# transmitter.net
KiCad netlist of a schematic drawn in EAGLE
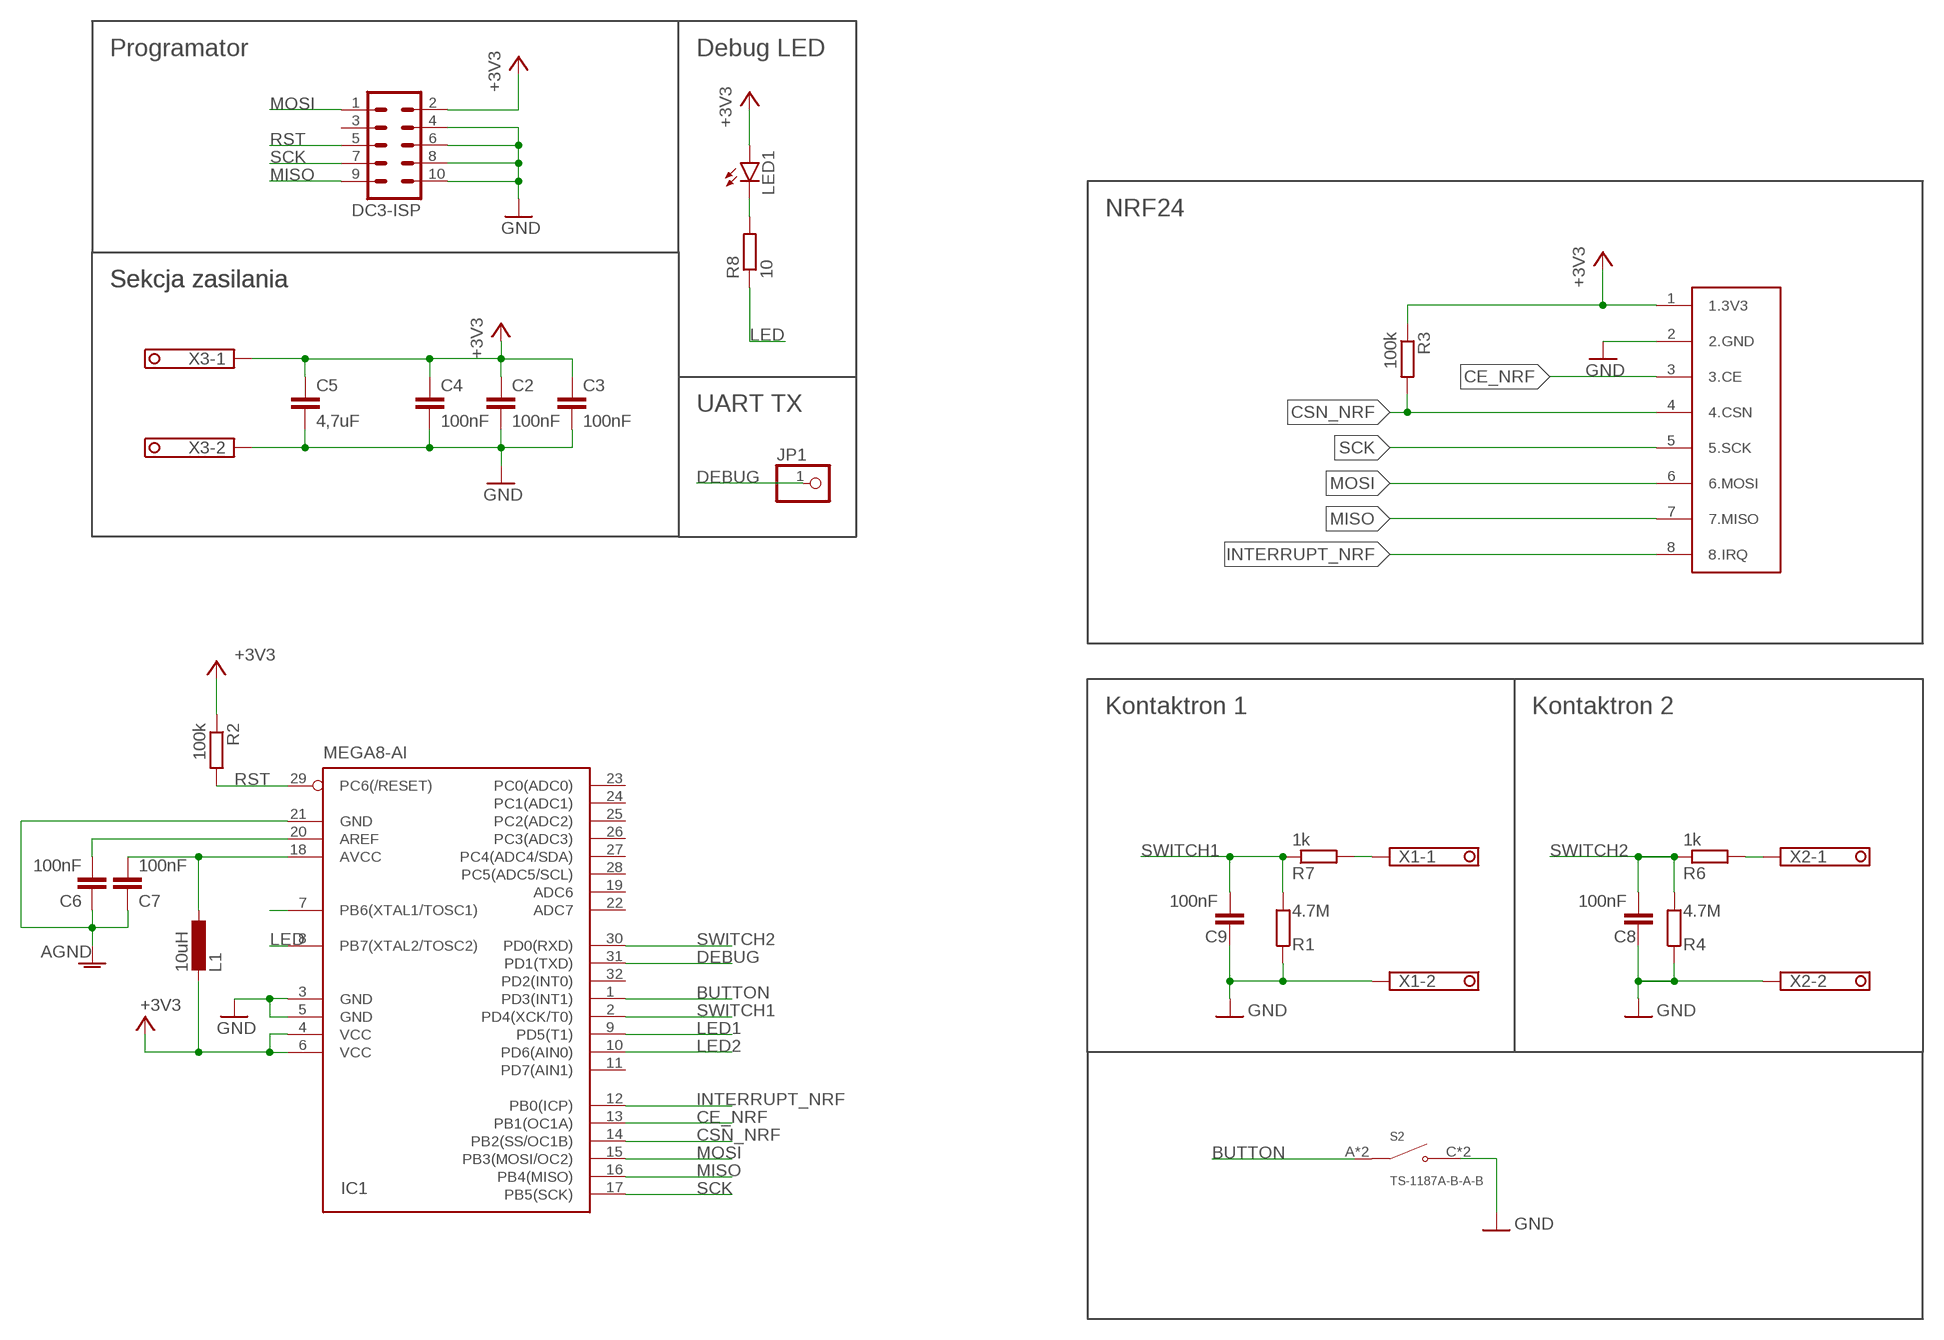
[diagram p0: schematic, sheet 1]

(export (version "E")
  (design (tool "Eeschema 10.0.6"))
  (components
    (comp (ref "C2")
      (value "100nF")
      (footprint "eagle-import:C0805")
      (libsource (lib "eagle-import") (part "C-EUC0805"))
    )
    (comp (ref "C3")
      (value "100nF")
      (footprint "eagle-import:C0805")
      (libsource (lib "eagle-import") (part "C-EUC0805"))
    )
    (comp (ref "C4")
      (value "100nF")
      (footprint "eagle-import:C0805")
      (libsource (lib "eagle-import") (part "C-EUC0805"))
    )
    (comp (ref "C5")
      (value "4,7uF")
      (footprint "eagle-import:C025-050X050")
      (libsource (lib "eagle-import") (part "C-EU025-050X050"))
    )
    (comp (ref "C6")
      (value "100nF")
      (footprint "eagle-import:C0805")
      (libsource (lib "eagle-import") (part "C-EUC0805"))
    )
    (comp (ref "C7")
      (value "100nF")
      (footprint "eagle-import:C0805")
      (libsource (lib "eagle-import") (part "C-EUC0805"))
    )
    (comp (ref "C8")
      (value "100nF")
      (footprint "eagle-import:C0805")
      (libsource (lib "eagle-import") (part "C-EUC0805"))
    )
    (comp (ref "C9")
      (value "100nF")
      (footprint "eagle-import:C0805")
      (libsource (lib "eagle-import") (part "C-EUC0805"))
    )
    (comp (ref "DC3-ISP")
      (value "ML10")
      (footprint "eagle-import:ML10")
      (libsource (lib "eagle-import") (part "ML10"))
    )
    (comp (ref "IC1")
      (value "MEGA8-AI")
      (footprint "eagle-import:TQFP32-08")
      (fields (field (name "MPN") "ATMEGA8-16AU"))
      (libsource (lib "eagle-import") (part "MEGA8-AI"))
    )
    (comp (ref "JP1")
      (value "PINHD-1X1")
      (footprint "eagle-import:1X01")
      (libsource (lib "eagle-import") (part "PINHD-1X1"))
    )
    (comp (ref "L1")
      (value "10uH")
      (footprint "eagle-import:L2012C")
      (libsource (lib "eagle-import") (part "L-EUL2012C"))
    )
    (comp (ref "LED1")
      (value "LEDCHIP-LED0805")
      (footprint "eagle-import:CHIP-LED0805")
      (libsource (lib "eagle-import") (part "LEDCHIP-LED0805"))
    )
    (comp (ref "R1")
      (value "4.7M")
      (footprint "eagle-import:M0805")
      (libsource (lib "eagle-import") (part "R-EU_M0805"))
    )
    (comp (ref "R2")
      (value "100k")
      (footprint "eagle-import:M0805")
      (libsource (lib "eagle-import") (part "R-EU_M0805"))
    )
    (comp (ref "R3")
      (value "100k")
      (footprint "eagle-import:M0805")
      (libsource (lib "eagle-import") (part "R-EU_M0805"))
    )
    (comp (ref "R4")
      (value "4.7M")
      (footprint "eagle-import:M0805")
      (libsource (lib "eagle-import") (part "R-EU_M0805"))
    )
    (comp (ref "R6")
      (value "1k")
      (footprint "eagle-import:M0805")
      (libsource (lib "eagle-import") (part "R-EU_M0805"))
    )
    (comp (ref "R7")
      (value "1k")
      (footprint "eagle-import:M0805")
      (libsource (lib "eagle-import") (part "R-EU_M0805"))
    )
    (comp (ref "R8")
      (value "10")
      (footprint "eagle-import:M0805")
      (libsource (lib "eagle-import") (part "R-EU_M0805"))
    )
    (comp (ref "S2")
      (value "TS-1187A-B-A-B")
      (footprint "eagle-import:SW_TS-1187A-B-A-B")
      (libsource (lib "eagle-import") (part "TS-1187A-B-A-B"))
    )
    (comp (ref "U$1")
      (value "NRF24L01+")
      (footprint "eagle-import:NRF24L01+")
      (libsource (lib "eagle-import") (part "NRF24L01+"))
    )
    (comp (ref "X1")
      (value "ARK-3.5MMAPC2")
      (footprint "eagle-import:1751248")
      (libsource (lib "eagle-import") (part "ARK-3.5MMAPC2"))
    )
    (comp (ref "X2")
      (value "ARK-3.5MMAPC2")
      (footprint "eagle-import:1751248")
      (libsource (lib "eagle-import") (part "ARK-3.5MMAPC2"))
    )
    (comp (ref "X3")
      (value "ARK-3.5MMAPC2")
      (footprint "eagle-import:1751248")
      (libsource (lib "eagle-import") (part "ARK-3.5MMAPC2"))
    )
  )
  (nets
    (net (code "1") (name "+3V3") (class "Default")
      (node (ref "C2") (pin "1") (pinfunction "1_1") (pintype "passive"))
      (node (ref "C3") (pin "1") (pinfunction "1_1") (pintype "passive"))
      (node (ref "C4") (pin "1") (pinfunction "1_1") (pintype "passive"))
      (node (ref "C5") (pin "1") (pinfunction "1_1") (pintype "passive"))
      (node (ref "DC3-ISP") (pin "2") (pinfunction "2_2") (pintype "passive"))
      (node (ref "IC1") (pin "4") (pinfunction "VCC_4") (pintype "power_in"))
      (node (ref "IC1") (pin "6") (pinfunction "VCC_6") (pintype "power_in"))
      (node (ref "L1") (pin "2") (pinfunction "2_2") (pintype "passive"))
      (node (ref "LED1") (pin "A") (pinfunction "A_A") (pintype "passive"))
      (node (ref "R2") (pin "1") (pinfunction "1_1") (pintype "passive"))
      (node (ref "R3") (pin "1") (pinfunction "1_1") (pintype "passive"))
      (node (ref "U$1") (pin "1") (pinfunction "1.3V3_1") (pintype "bidirectional"))
      (node (ref "X3") (pin "1") (pinfunction "K_1") (pintype "passive"))
    )
    (net (code "2") (name "/BUTTON") (class "Default")
      (node (ref "IC1") (pin "1") (pinfunction "PD3(INT1)_1") (pintype "bidirectional"))
      (node (ref "S2") (pin "A") (pinfunction "COM_A") (pintype "passive"))
      (node (ref "S2") (pin "B") (pinfunction "COM_B") (pintype "passive"))
    )
    (net (code "3") (name "/DEBUG") (class "Default")
      (node (ref "IC1") (pin "31") (pinfunction "PD1(TXD)_31") (pintype "bidirectional"))
      (node (ref "JP1") (pin "1") (pinfunction "1_1") (pintype "passive"))
    )
    (net (code "4") (name "/LED") (class "Default")
      (node (ref "IC1") (pin "8") (pinfunction "PB7(XTAL2/TOSC2)_8") (pintype "bidirectional"))
      (node (ref "R8") (pin "1") (pinfunction "1_1") (pintype "passive"))
    )
    (net (code "5") (name "/LED1") (class "Default")
      (node (ref "IC1") (pin "9") (pinfunction "PD5(T1)_9") (pintype "bidirectional"))
    )
    (net (code "6") (name "/LED2") (class "Default")
      (node (ref "IC1") (pin "10") (pinfunction "PD6(AIN0)_10") (pintype "bidirectional"))
    )
    (net (code "7") (name "/RST") (class "Default")
      (node (ref "DC3-ISP") (pin "5") (pinfunction "5_5") (pintype "passive"))
      (node (ref "IC1") (pin "29") (pinfunction "PC6(/RESET)_29") (pintype "bidirectional"))
      (node (ref "R2") (pin "2") (pinfunction "2_2") (pintype "passive"))
    )
    (net (code "8") (name "/SWITCH1") (class "Default")
      (node (ref "C9") (pin "2") (pinfunction "2_2") (pintype "passive"))
      (node (ref "IC1") (pin "2") (pinfunction "PD4(XCK/T0)_2") (pintype "bidirectional"))
      (node (ref "R1") (pin "2") (pinfunction "2_2") (pintype "passive"))
      (node (ref "R7") (pin "1") (pinfunction "1_1") (pintype "passive"))
    )
    (net (code "9") (name "/SWITCH2") (class "Default")
      (node (ref "C8") (pin "2") (pinfunction "2_2") (pintype "passive"))
      (node (ref "IC1") (pin "30") (pinfunction "PD0(RXD)_30") (pintype "bidirectional"))
      (node (ref "R4") (pin "2") (pinfunction "2_2") (pintype "passive"))
      (node (ref "R6") (pin "1") (pinfunction "1_1") (pintype "passive"))
    )
    (net (code "10") (name "AGND") (class "Default")
      (node (ref "C6") (pin "1") (pinfunction "1_1") (pintype "passive"))
      (node (ref "C7") (pin "1") (pinfunction "1_1") (pintype "passive"))
      (node (ref "IC1") (pin "21") (pinfunction "GND_21") (pintype "power_in"))
    )
    (net (code "11") (name "CE_NRF") (class "Default")
      (node (ref "IC1") (pin "13") (pinfunction "PB1(OC1A)_13") (pintype "bidirectional"))
      (node (ref "U$1") (pin "3") (pinfunction "3.CE_3") (pintype "bidirectional"))
    )
    (net (code "12") (name "CSN_NRF") (class "Default")
      (node (ref "IC1") (pin "14") (pinfunction "PB2(SS/OC1B)_14") (pintype "bidirectional"))
      (node (ref "R3") (pin "2") (pinfunction "2_2") (pintype "passive"))
      (node (ref "U$1") (pin "4") (pinfunction "4.CSN_4") (pintype "bidirectional"))
    )
    (net (code "13") (name "GND") (class "Default")
      (node (ref "C2") (pin "2") (pinfunction "2_2") (pintype "passive"))
      (node (ref "C3") (pin "2") (pinfunction "2_2") (pintype "passive"))
      (node (ref "C4") (pin "2") (pinfunction "2_2") (pintype "passive"))
      (node (ref "C5") (pin "2") (pinfunction "2_2") (pintype "passive"))
      (node (ref "C8") (pin "1") (pinfunction "1_1") (pintype "passive"))
      (node (ref "C9") (pin "1") (pinfunction "1_1") (pintype "passive"))
      (node (ref "DC3-ISP") (pin "10") (pinfunction "10_10") (pintype "passive"))
      (node (ref "DC3-ISP") (pin "4") (pinfunction "4_4") (pintype "passive"))
      (node (ref "DC3-ISP") (pin "6") (pinfunction "6_6") (pintype "passive"))
      (node (ref "DC3-ISP") (pin "8") (pinfunction "8_8") (pintype "passive"))
      (node (ref "IC1") (pin "3") (pinfunction "GND_3") (pintype "power_in"))
      (node (ref "IC1") (pin "5") (pinfunction "GND_5") (pintype "power_in"))
      (node (ref "R1") (pin "1") (pinfunction "1_1") (pintype "passive"))
      (node (ref "R4") (pin "1") (pinfunction "1_1") (pintype "passive"))
      (node (ref "S2") (pin "C") (pinfunction "NO_C") (pintype "passive"))
      (node (ref "S2") (pin "D") (pinfunction "NO_D") (pintype "passive"))
      (node (ref "U$1") (pin "2") (pinfunction "2.GND_2") (pintype "bidirectional"))
      (node (ref "X1") (pin "2") (pinfunction "K_2") (pintype "passive"))
      (node (ref "X2") (pin "2") (pinfunction "K_2") (pintype "passive"))
      (node (ref "X3") (pin "2") (pinfunction "K_2") (pintype "passive"))
    )
    (net (code "14") (name "INTERRUPT_NRF") (class "Default")
      (node (ref "IC1") (pin "12") (pinfunction "PB0(ICP)_12") (pintype "bidirectional"))
      (node (ref "U$1") (pin "8") (pinfunction "8.IRQ_8") (pintype "bidirectional"))
    )
    (net (code "15") (name "MISO") (class "Default")
      (node (ref "DC3-ISP") (pin "9") (pinfunction "9_9") (pintype "passive"))
      (node (ref "IC1") (pin "16") (pinfunction "PB4(MISO)_16") (pintype "bidirectional"))
      (node (ref "U$1") (pin "7") (pinfunction "7.MISO_7") (pintype "bidirectional"))
    )
    (net (code "16") (name "MOSI") (class "Default")
      (node (ref "DC3-ISP") (pin "1") (pinfunction "1_1") (pintype "passive"))
      (node (ref "IC1") (pin "15") (pinfunction "PB3(MOSI/OC2)_15") (pintype "bidirectional"))
      (node (ref "U$1") (pin "6") (pinfunction "6.MOSI_6") (pintype "bidirectional"))
    )
    (net (code "17") (name "Net-(IC1-AREF)") (class "Default")
      (node (ref "C6") (pin "2") (pinfunction "2_2") (pintype "passive"))
      (node (ref "IC1") (pin "20") (pinfunction "AREF_20") (pintype "passive"))
    )
    (net (code "18") (name "Net-(IC1-AVCC)") (class "Default")
      (node (ref "C7") (pin "2") (pinfunction "2_2") (pintype "passive"))
      (node (ref "IC1") (pin "18") (pinfunction "AVCC_18") (pintype "power_in"))
      (node (ref "L1") (pin "1") (pinfunction "1_1") (pintype "passive"))
    )
    (net (code "19") (name "Net-(LED1-PadC)") (class "Default")
      (node (ref "LED1") (pin "C") (pinfunction "C_C") (pintype "passive"))
      (node (ref "R8") (pin "2") (pinfunction "2_2") (pintype "passive"))
    )
    (net (code "20") (name "Net-(X1A-K)") (class "Default")
      (node (ref "R7") (pin "2") (pinfunction "2_2") (pintype "passive"))
      (node (ref "X1") (pin "1") (pinfunction "K_1") (pintype "passive"))
    )
    (net (code "21") (name "Net-(X2A-K)") (class "Default")
      (node (ref "R6") (pin "2") (pinfunction "2_2") (pintype "passive"))
      (node (ref "X2") (pin "1") (pinfunction "K_1") (pintype "passive"))
    )
    (net (code "22") (name "SCK") (class "Default")
      (node (ref "DC3-ISP") (pin "7") (pinfunction "7_7") (pintype "passive"))
      (node (ref "IC1") (pin "17") (pinfunction "PB5(SCK)_17") (pintype "bidirectional"))
      (node (ref "U$1") (pin "5") (pinfunction "5.SCK_5") (pintype "bidirectional"))
    )
    (net (code "23") (name "unconnected-(DC3-ISP-Pad3)") (class "Default")
      (node (ref "DC3-ISP") (pin "3") (pinfunction "3_3") (pintype "passive"))
    )
    (net (code "24") (name "unconnected-(IC1-ADC6-Pad19)") (class "Default")
      (node (ref "IC1") (pin "19") (pinfunction "ADC6_19") (pintype "bidirectional"))
    )
    (net (code "25") (name "unconnected-(IC1-ADC7-Pad22)") (class "Default")
      (node (ref "IC1") (pin "22") (pinfunction "ADC7_22") (pintype "bidirectional"))
    )
    (net (code "26") (name "unconnected-(IC1-PB6(XTAL1{slash}TOSC1)-Pad7)") (class "Default")
      (node (ref "IC1") (pin "7") (pinfunction "PB6(XTAL1/TOSC1)_7") (pintype "bidirectional"))
    )
    (net (code "27") (name "unconnected-(IC1-PC0(ADC0)-Pad23)") (class "Default")
      (node (ref "IC1") (pin "23") (pinfunction "PC0(ADC0)_23") (pintype "bidirectional"))
    )
    (net (code "28") (name "unconnected-(IC1-PC1(ADC1)-Pad24)") (class "Default")
      (node (ref "IC1") (pin "24") (pinfunction "PC1(ADC1)_24") (pintype "bidirectional"))
    )
    (net (code "29") (name "unconnected-(IC1-PC2(ADC2)-Pad25)") (class "Default")
      (node (ref "IC1") (pin "25") (pinfunction "PC2(ADC2)_25") (pintype "bidirectional"))
    )
    (net (code "30") (name "unconnected-(IC1-PC3(ADC3)-Pad26)") (class "Default")
      (node (ref "IC1") (pin "26") (pinfunction "PC3(ADC3)_26") (pintype "bidirectional"))
    )
    (net (code "31") (name "unconnected-(IC1-PC4(ADC4{slash}SDA)-Pad27)") (class "Default")
      (node (ref "IC1") (pin "27") (pinfunction "PC4(ADC4/SDA)_27") (pintype "bidirectional"))
    )
    (net (code "32") (name "unconnected-(IC1-PC5(ADC5{slash}SCL)-Pad28)") (class "Default")
      (node (ref "IC1") (pin "28") (pinfunction "PC5(ADC5/SCL)_28") (pintype "bidirectional"))
    )
    (net (code "33") (name "unconnected-(IC1-PD2(INT0)-Pad32)") (class "Default")
      (node (ref "IC1") (pin "32") (pinfunction "PD2(INT0)_32") (pintype "bidirectional"))
    )
    (net (code "34") (name "unconnected-(IC1-PD7(AIN1)-Pad11)") (class "Default")
      (node (ref "IC1") (pin "11") (pinfunction "PD7(AIN1)_11") (pintype "bidirectional"))
    )
  )
)
